# Sensing.net
KiCad netlist of a schematic drawn in Altium Designer
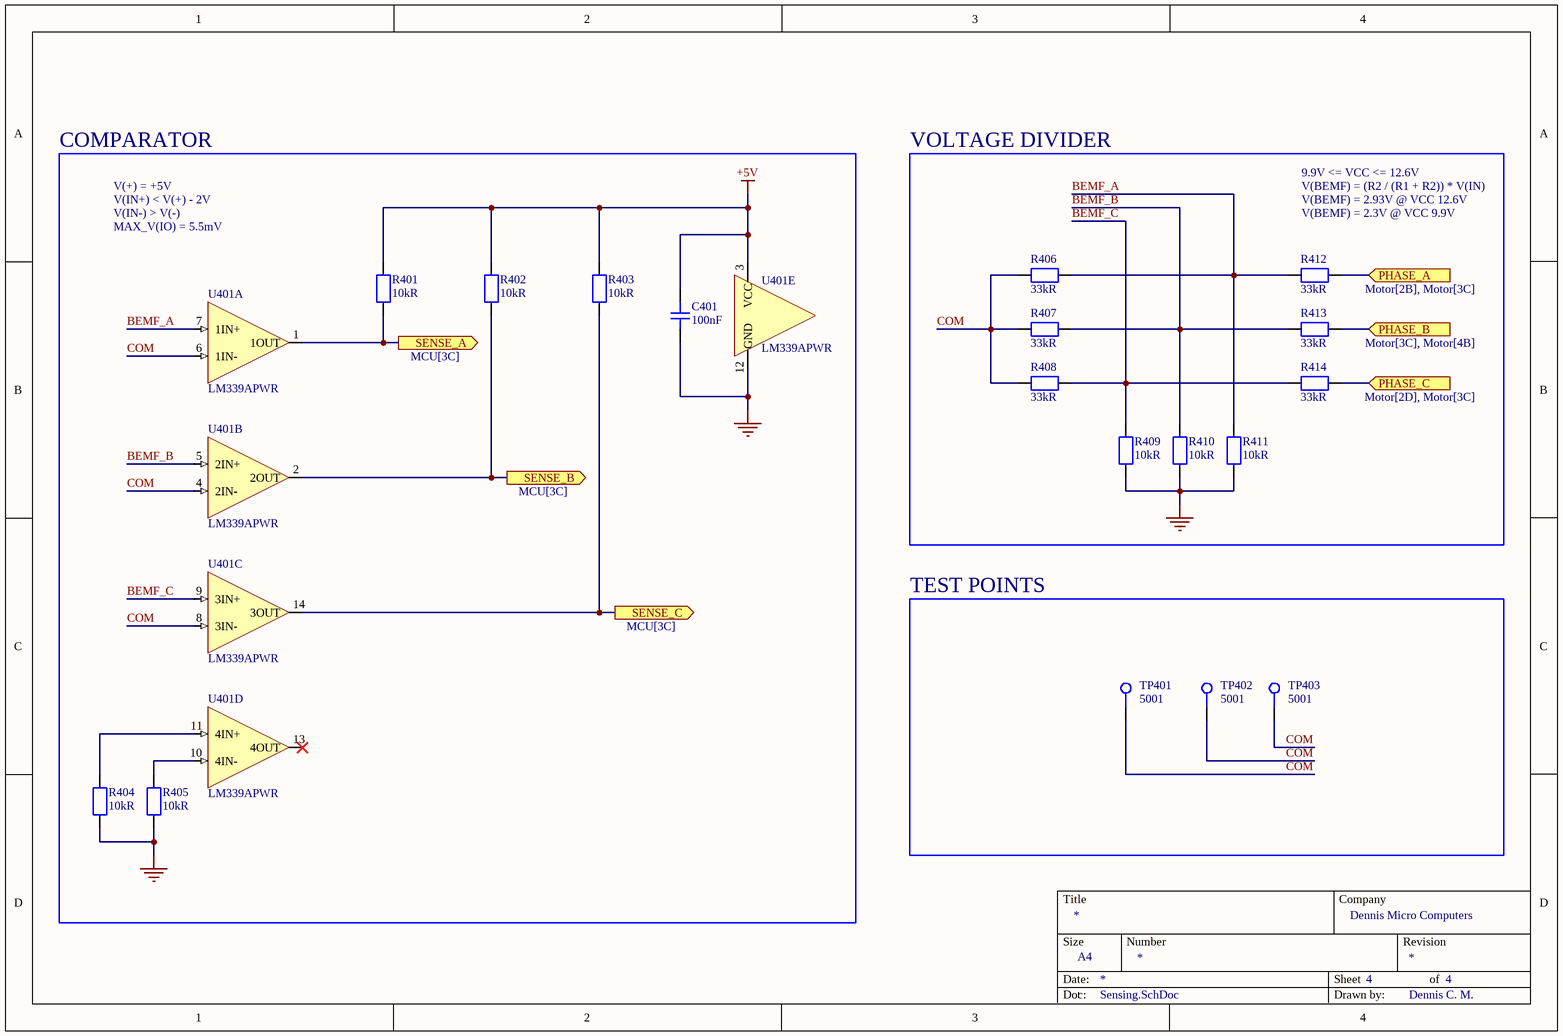
[diagram p0: Sensing.SchDoc]

(export (version "E")
  (design (tool "Eeschema 10.0.6"))
  (components
    (comp (ref "C401")
      (value "100nF")
      (footprint "C_Yageo_CC_0402_A")
      (description "Multilayer Ceramic Capacitor, 0.1 uF, 10 V, ± 20%, X7R, 0402 [1005 Metric]")
      (fields (field (name "TOLERANCE") "20%") (field (name "Comment") "CC0402MRX5R6BB104"))
      (libsource (lib "Dennis Micro Computers") (part "C"))
    )
    (comp (ref "R401")
      (value "10kR")
      (footprint "R_Yageo_RCL_0402_A")
      (description "SMD Chip Resistor, 10 kOhm, ± 1%, 62.5 mW, 0402 [1005 Metric], Thick Film, General Purpose")
      (fields (field (name "TOLERANCE") "1%") (field (name "Comment") "RC0402FR-0710KL"))
      (libsource (lib "Dennis Micro Computers") (part "R"))
    )
    (comp (ref "R402")
      (value "10kR")
      (footprint "R_Yageo_RCL_0402_A")
      (description "SMD Chip Resistor, 10 kOhm, ± 1%, 62.5 mW, 0402 [1005 Metric], Thick Film, General Purpose")
      (fields (field (name "TOLERANCE") "1%") (field (name "Comment") "RC0402FR-0710KL"))
      (libsource (lib "Dennis Micro Computers") (part "R"))
    )
    (comp (ref "R403")
      (value "10kR")
      (footprint "R_Yageo_RCL_0402_A")
      (description "SMD Chip Resistor, 10 kOhm, ± 1%, 62.5 mW, 0402 [1005 Metric], Thick Film, General Purpose")
      (fields (field (name "TOLERANCE") "1%") (field (name "Comment") "RC0402FR-0710KL"))
      (libsource (lib "Dennis Micro Computers") (part "R"))
    )
    (comp (ref "R404")
      (value "10kR")
      (footprint "R_Yageo_RCL_0402_A")
      (description "SMD Chip Resistor, 10 kOhm, ± 1%, 62.5 mW, 0402 [1005 Metric], Thick Film, General Purpose")
      (fields (field (name "TOLERANCE") "1%") (field (name "Comment") "RC0402FR-0710KL"))
      (libsource (lib "Dennis Micro Computers") (part "R"))
    )
    (comp (ref "R405")
      (value "10kR")
      (footprint "R_Yageo_RCL_0402_A")
      (description "SMD Chip Resistor, 10 kOhm, ± 1%, 62.5 mW, 0402 [1005 Metric], Thick Film, General Purpose")
      (fields (field (name "TOLERANCE") "1%") (field (name "Comment") "RC0402FR-0710KL"))
      (libsource (lib "Dennis Micro Computers") (part "R"))
    )
    (comp (ref "R406")
      (value "33kR")
      (footprint "R_Yageo_RCL_0402_A")
      (description "SMD Chip Resistor, 33 kOhm, ± 1%, 63 mW, 0402 [1005 Metric], Thick Film, General Purpose")
      (fields (field (name "TOLERANCE") "1%") (field (name "Comment") "RC0402FR-0733KL"))
      (libsource (lib "Dennis Micro Computers") (part "R"))
    )
    (comp (ref "R407")
      (value "33kR")
      (footprint "R_Yageo_RCL_0402_A")
      (description "SMD Chip Resistor, 33 kOhm, ± 1%, 63 mW, 0402 [1005 Metric], Thick Film, General Purpose")
      (fields (field (name "TOLERANCE") "1%") (field (name "Comment") "RC0402FR-0733KL"))
      (libsource (lib "Dennis Micro Computers") (part "R"))
    )
    (comp (ref "R408")
      (value "33kR")
      (footprint "R_Yageo_RCL_0402_A")
      (description "SMD Chip Resistor, 33 kOhm, ± 1%, 63 mW, 0402 [1005 Metric], Thick Film, General Purpose")
      (fields (field (name "TOLERANCE") "1%") (field (name "Comment") "RC0402FR-0733KL"))
      (libsource (lib "Dennis Micro Computers") (part "R"))
    )
    (comp (ref "R409")
      (value "10kR")
      (footprint "R_Yageo_RCL_0402_A")
      (description "SMD Chip Resistor, 10 kOhm, ± 1%, 62.5 mW, 0402 [1005 Metric], Thick Film, General Purpose")
      (fields (field (name "TOLERANCE") "1%") (field (name "Comment") "RC0402FR-0710KL"))
      (libsource (lib "Dennis Micro Computers") (part "R"))
    )
    (comp (ref "R410")
      (value "10kR")
      (footprint "R_Yageo_RCL_0402_A")
      (description "SMD Chip Resistor, 10 kOhm, ± 1%, 62.5 mW, 0402 [1005 Metric], Thick Film, General Purpose")
      (fields (field (name "TOLERANCE") "1%") (field (name "Comment") "RC0402FR-0710KL"))
      (libsource (lib "Dennis Micro Computers") (part "R"))
    )
    (comp (ref "R411")
      (value "10kR")
      (footprint "R_Yageo_RCL_0402_A")
      (description "SMD Chip Resistor, 10 kOhm, ± 1%, 62.5 mW, 0402 [1005 Metric], Thick Film, General Purpose")
      (fields (field (name "TOLERANCE") "1%") (field (name "Comment") "RC0402FR-0710KL"))
      (libsource (lib "Dennis Micro Computers") (part "R"))
    )
    (comp (ref "R412")
      (value "33kR")
      (footprint "R_Yageo_RCL_0402_A")
      (description "SMD Chip Resistor, 33 kOhm, ± 1%, 63 mW, 0402 [1005 Metric], Thick Film, General Purpose")
      (fields (field (name "TOLERANCE") "1%") (field (name "Comment") "RC0402FR-0733KL"))
      (libsource (lib "Dennis Micro Computers") (part "R"))
    )
    (comp (ref "R413")
      (value "33kR")
      (footprint "R_Yageo_RCL_0402_A")
      (description "SMD Chip Resistor, 33 kOhm, ± 1%, 63 mW, 0402 [1005 Metric], Thick Film, General Purpose")
      (fields (field (name "TOLERANCE") "1%") (field (name "Comment") "RC0402FR-0733KL"))
      (libsource (lib "Dennis Micro Computers") (part "R"))
    )
    (comp (ref "R414")
      (value "33kR")
      (footprint "R_Yageo_RCL_0402_A")
      (description "SMD Chip Resistor, 33 kOhm, ± 1%, 63 mW, 0402 [1005 Metric], Thick Film, General Purpose")
      (fields (field (name "TOLERANCE") "1%") (field (name "Comment") "RC0402FR-0733KL"))
      (libsource (lib "Dennis Micro Computers") (part "R"))
    )
    (comp (ref "TP401")
      (value "5001")
      (footprint "TP_Keystone_TH")
      (libsource (lib "Dennis Micro Computers") (part "TP"))
    )
    (comp (ref "TP402")
      (value "5001")
      (footprint "TP_Keystone_TH")
      (libsource (lib "Dennis Micro Computers") (part "TP"))
    )
    (comp (ref "TP403")
      (value "5001")
      (footprint "TP_Keystone_TH")
      (libsource (lib "Dennis Micro Computers") (part "TP"))
    )
    (comp (ref "U401")
      (value "LM339APWR")
      (footprint "U_TI_14-TSSOP-5.00x4.40mm_0.62mm_B")
      (description "Precision quad differential comparator, commercial grade 14-TSSOP 0 to 70")
      (libsource (lib "Dennis Micro Computers") (part "U_LM339APWR"))
    )
  )
  (nets
    (net (code "1") (name "+5V") (class "Default")
      (node (ref "C401") (pin "2") (pinfunction "2_2") (pintype "passive"))
      (node (ref "R401") (pin "2") (pinfunction "2_2") (pintype "passive"))
      (node (ref "R402") (pin "2") (pinfunction "2_2") (pintype "passive"))
      (node (ref "R403") (pin "2") (pinfunction "2_2") (pintype "passive"))
      (node (ref "U401") (pin "3") (pinfunction "VCC_3") (pintype "power_in"))
    )
    (net (code "2") (name "/BEMF_A") (class "Default")
      (node (ref "R406") (pin "2") (pinfunction "2_2") (pintype "passive"))
      (node (ref "R411") (pin "2") (pinfunction "2_2") (pintype "passive"))
      (node (ref "R412") (pin "1") (pinfunction "1_1") (pintype "passive"))
      (node (ref "U401") (pin "7") (pinfunction "1IN+_7") (pintype "input"))
    )
    (net (code "3") (name "/BEMF_B") (class "Default")
      (node (ref "R407") (pin "2") (pinfunction "2_2") (pintype "passive"))
      (node (ref "R410") (pin "2") (pinfunction "2_2") (pintype "passive"))
      (node (ref "R413") (pin "1") (pinfunction "1_1") (pintype "passive"))
      (node (ref "U401") (pin "5") (pinfunction "2IN+_5") (pintype "input"))
    )
    (net (code "4") (name "/BEMF_C") (class "Default")
      (node (ref "R408") (pin "2") (pinfunction "2_2") (pintype "passive"))
      (node (ref "R409") (pin "2") (pinfunction "2_2") (pintype "passive"))
      (node (ref "R414") (pin "1") (pinfunction "1_1") (pintype "passive"))
      (node (ref "U401") (pin "9") (pinfunction "3IN+_9") (pintype "input"))
    )
    (net (code "5") (name "/COM") (class "Default")
      (node (ref "R406") (pin "1") (pinfunction "1_1") (pintype "passive"))
      (node (ref "R407") (pin "1") (pinfunction "1_1") (pintype "passive"))
      (node (ref "R408") (pin "1") (pinfunction "1_1") (pintype "passive"))
      (node (ref "TP401") (pin "1") (pinfunction "1_1") (pintype "passive"))
      (node (ref "TP402") (pin "1") (pinfunction "1_1") (pintype "passive"))
      (node (ref "TP403") (pin "1") (pinfunction "1_1") (pintype "passive"))
      (node (ref "U401") (pin "4") (pinfunction "2IN-_4") (pintype "input"))
      (node (ref "U401") (pin "6") (pinfunction "1IN-_6") (pintype "input"))
      (node (ref "U401") (pin "8") (pinfunction "3IN-_8") (pintype "input"))
    )
    (net (code "6") (name "/PHASE_A") (class "Default")
      (node (ref "R412") (pin "2") (pinfunction "2_2") (pintype "passive"))
    )
    (net (code "7") (name "/PHASE_B") (class "Default")
      (node (ref "R413") (pin "2") (pinfunction "2_2") (pintype "passive"))
    )
    (net (code "8") (name "/PHASE_C") (class "Default")
      (node (ref "R414") (pin "2") (pinfunction "2_2") (pintype "passive"))
    )
    (net (code "9") (name "/SENSE_A") (class "Default")
      (node (ref "R401") (pin "1") (pinfunction "1_1") (pintype "passive"))
      (node (ref "U401") (pin "1") (pinfunction "1OUT_1") (pintype "open_collector"))
    )
    (net (code "10") (name "/SENSE_B") (class "Default")
      (node (ref "R402") (pin "1") (pinfunction "1_1") (pintype "passive"))
      (node (ref "U401") (pin "2") (pinfunction "2OUT_2") (pintype "open_collector"))
    )
    (net (code "11") (name "/SENSE_C") (class "Default")
      (node (ref "R403") (pin "1") (pinfunction "1_1") (pintype "passive"))
      (node (ref "U401") (pin "14") (pinfunction "3OUT_14") (pintype "open_collector"))
    )
    (net (code "12") (name "GND") (class "Default")
      (node (ref "C401") (pin "1") (pinfunction "1_1") (pintype "passive"))
      (node (ref "R404") (pin "1") (pinfunction "1_1") (pintype "passive"))
      (node (ref "R405") (pin "1") (pinfunction "1_1") (pintype "passive"))
      (node (ref "R409") (pin "1") (pinfunction "1_1") (pintype "passive"))
      (node (ref "R410") (pin "1") (pinfunction "1_1") (pintype "passive"))
      (node (ref "R411") (pin "1") (pinfunction "1_1") (pintype "passive"))
      (node (ref "U401") (pin "12") (pinfunction "GND_12") (pintype "power_in"))
    )
    (net (code "13") (name "Net-(U401D-4IN+)") (class "Default")
      (node (ref "R404") (pin "2") (pinfunction "2_2") (pintype "passive"))
      (node (ref "U401") (pin "11") (pinfunction "4IN+_11") (pintype "input"))
    )
    (net (code "14") (name "Net-(U401D-4IN-)") (class "Default")
      (node (ref "R405") (pin "2") (pinfunction "2_2") (pintype "passive"))
      (node (ref "U401") (pin "10") (pinfunction "4IN-_10") (pintype "input"))
    )
    (net (code "15") (name "unconnected-(U401D-4OUT-Pad13)") (class "Default")
      (node (ref "U401") (pin "13") (pinfunction "4OUT_13") (pintype "open_collector+no_connect"))
    )
  )
)
